# IRRemoteWand.net
KiCad netlist of a schematic drawn in EAGLE
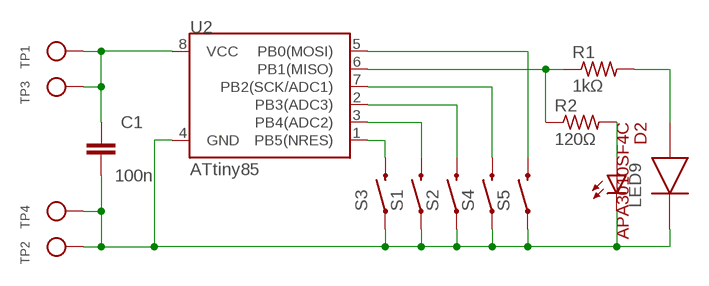
[diagram p0: schematic, sheet 1]

(export (version "E")
  (design (tool "Eeschema 10.0.6"))
  (components
    (comp (ref "C1")
      (value "100n")
      (footprint "eagle-import:0603-CAP")
      (libsource (lib "eagle-import") (part "CAP0603-CAP"))
    )
    (comp (ref "D2")
      (value "APA3010SF4C")
      (footprint "eagle-import:APA3010SF4C")
      (libsource (lib "eagle-import") (part "APA3010SF4C"))
    )
    (comp (ref "LED9")
      (value "LEDCHIPLED_0805")
      (footprint "eagle-import:CHIPLED_0805")
      (libsource (lib "eagle-import") (part "LEDCHIPLED_0805"))
    )
    (comp (ref "R1")
      (value "1kΩ")
      (footprint "eagle-import:M0805")
      (libsource (lib "eagle-import") (part "R-US_M0805"))
    )
    (comp (ref "R2")
      (value "120Ω")
      (footprint "eagle-import:M0805")
      (libsource (lib "eagle-import") (part "R-US_M0805"))
    )
    (comp (ref "S1")
      (value "SWITCH-MOMENTARY-2SMD-4")
      (footprint "eagle-import:TACTILE_SWITCH_TALL")
      (libsource (lib "eagle-import") (part "SWITCH-MOMENTARY-2SMD-4"))
    )
    (comp (ref "S2")
      (value "SWITCH-MOMENTARY-2SMD-4")
      (footprint "eagle-import:TACTILE_SWITCH_TALL")
      (libsource (lib "eagle-import") (part "SWITCH-MOMENTARY-2SMD-4"))
    )
    (comp (ref "S3")
      (value "SWITCH-MOMENTARY-2SMD-4")
      (footprint "eagle-import:TACTILE_SWITCH_TALL")
      (libsource (lib "eagle-import") (part "SWITCH-MOMENTARY-2SMD-4"))
    )
    (comp (ref "S4")
      (value "SWITCH-MOMENTARY-2SMD-4")
      (footprint "eagle-import:TACTILE_SWITCH_TALL")
      (libsource (lib "eagle-import") (part "SWITCH-MOMENTARY-2SMD-4"))
    )
    (comp (ref "S5")
      (value "SWITCH-MOMENTARY-2SMD-4")
      (footprint "eagle-import:TACTILE_SWITCH_TALL")
      (libsource (lib "eagle-import") (part "SWITCH-MOMENTARY-2SMD-4"))
    )
    (comp (ref "TP1")
      (value "TESTPOINTPAD")
      (footprint "eagle-import:TESTPOINT_PAD_2MM")
      (libsource (lib "eagle-import") (part "TESTPOINTPAD"))
    )
    (comp (ref "TP2")
      (value "TESTPOINTPAD")
      (footprint "eagle-import:TESTPOINT_PAD_2MM")
      (libsource (lib "eagle-import") (part "TESTPOINTPAD"))
    )
    (comp (ref "TP3")
      (value "TESTPOINTPAD")
      (footprint "eagle-import:TESTPOINT_PAD_2MM")
      (libsource (lib "eagle-import") (part "TESTPOINTPAD"))
    )
    (comp (ref "TP4")
      (value "TESTPOINTPAD")
      (footprint "eagle-import:TESTPOINT_PAD_2MM")
      (libsource (lib "eagle-import") (part "TESTPOINTPAD"))
    )
    (comp (ref "U2")
      (value "ATtiny85")
      (footprint "eagle-import:SO08-EIAJ")
      (libsource (lib "eagle-import") (part "ATTINY45TINY45-20-SMT"))
    )
  )
  (nets
    (net (code "1") (name "Net-(D2-Pad1)") (class "Default")
      (node (ref "D2") (pin "1") (pinfunction "1_1") (pintype "bidirectional"))
      (node (ref "R1") (pin "2") (pinfunction "2_2") (pintype "passive"))
    )
    (net (code "2") (name "Net-(LED9-PadA)") (class "Default")
      (node (ref "LED9") (pin "A") (pinfunction "A_A") (pintype "passive"))
      (node (ref "R2") (pin "2") (pinfunction "2_2") (pintype "passive"))
    )
    (net (code "3") (name "Net-(S1-1)") (class "Default")
      (node (ref "C1") (pin "2") (pinfunction "2_2") (pintype "passive"))
      (node (ref "D2") (pin "2") (pinfunction "2_2") (pintype "bidirectional"))
      (node (ref "LED9") (pin "C") (pinfunction "C_C") (pintype "passive"))
      (node (ref "S1") (pin "A2") (pinfunction "1_A2") (pintype "passive"))
      (node (ref "S2") (pin "A2") (pinfunction "1_A2") (pintype "passive"))
      (node (ref "S3") (pin "A2") (pinfunction "1_A2") (pintype "passive"))
      (node (ref "S4") (pin "A2") (pinfunction "1_A2") (pintype "passive"))
      (node (ref "S5") (pin "A2") (pinfunction "1_A2") (pintype "passive"))
      (node (ref "TP2") (pin "P$1") (pinfunction "P$1_P$1") (pintype "bidirectional"))
      (node (ref "TP4") (pin "P$1") (pinfunction "P$1_P$1") (pintype "bidirectional"))
      (node (ref "U2") (pin "4") (pinfunction "GND_4") (pintype "bidirectional"))
    )
    (net (code "4") (name "Net-(S1-2)") (class "Default")
      (node (ref "S1") (pin "B2") (pinfunction "2_B2") (pintype "passive"))
      (node (ref "U2") (pin "3") (pinfunction "PB4(ADC2)_3") (pintype "bidirectional"))
    )
    (net (code "5") (name "Net-(S2-2)") (class "Default")
      (node (ref "S2") (pin "B2") (pinfunction "2_B2") (pintype "passive"))
      (node (ref "U2") (pin "2") (pinfunction "PB3(ADC3)_2") (pintype "bidirectional"))
    )
    (net (code "6") (name "Net-(S3-2)") (class "Default")
      (node (ref "S3") (pin "B2") (pinfunction "2_B2") (pintype "passive"))
      (node (ref "U2") (pin "1") (pinfunction "PB5(NRES)_1") (pintype "bidirectional"))
    )
    (net (code "7") (name "Net-(S4-2)") (class "Default")
      (node (ref "S4") (pin "B2") (pinfunction "2_B2") (pintype "passive"))
      (node (ref "U2") (pin "7") (pinfunction "PB2(SCK/ADC1)_7") (pintype "bidirectional"))
    )
    (net (code "8") (name "Net-(S5-2)") (class "Default")
      (node (ref "S5") (pin "B2") (pinfunction "2_B2") (pintype "passive"))
      (node (ref "U2") (pin "5") (pinfunction "PB0(MOSI)_5") (pintype "bidirectional"))
    )
    (net (code "9") (name "Net-(U2-PB1(MISO))") (class "Default")
      (node (ref "R1") (pin "1") (pinfunction "1_1") (pintype "passive"))
      (node (ref "R2") (pin "1") (pinfunction "1_1") (pintype "passive"))
      (node (ref "U2") (pin "6") (pinfunction "PB1(MISO)_6") (pintype "bidirectional"))
    )
    (net (code "10") (name "Net-(U2-VCC)") (class "Default")
      (node (ref "C1") (pin "1") (pinfunction "1_1") (pintype "passive"))
      (node (ref "TP1") (pin "P$1") (pinfunction "P$1_P$1") (pintype "bidirectional"))
      (node (ref "TP3") (pin "P$1") (pinfunction "P$1_P$1") (pintype "bidirectional"))
      (node (ref "U2") (pin "8") (pinfunction "VCC_8") (pintype "bidirectional"))
    )
  )
)
